# Clock-management.net
KiCad netlist of a schematic drawn in Altium Designer
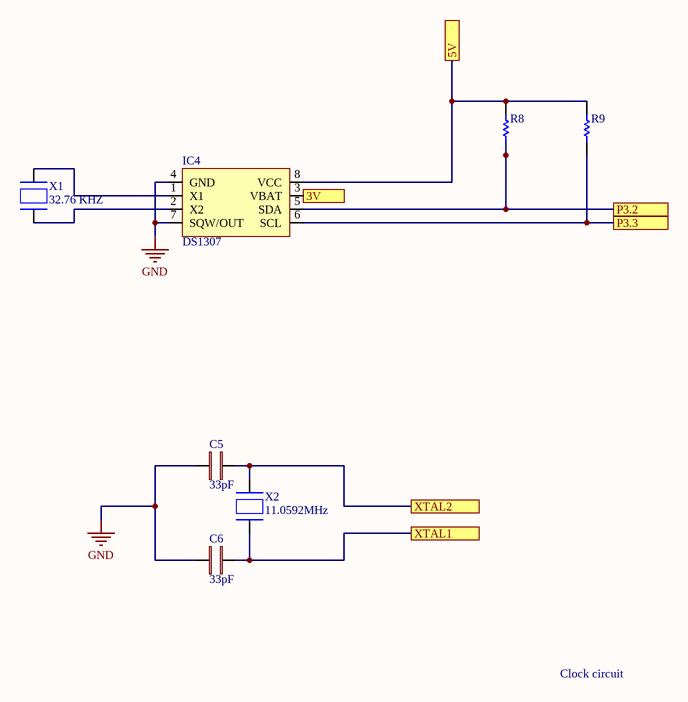
[diagram p0: Clock-management.SchDoc]

(export (version "E")
  (design (tool "Eeschema 10.0.6"))
  (components
    (comp (ref "C5")
      (value "33pF")
      (footprint "250R07S330JV4T")
      (description "Cap Ceramic 33pF 50V C0G 5% Pad SMD 0402 125°C Ultra Low ESR T/R")
      (fields
        (field (name "MANUFACTURER") "Johanson")
        (field (name "MANUFACTURER PART NUMBER") "500R07S330JV4T")
      )
      (libsource (lib "Tama_Schlib") (part "500R07S330JV4T"))
    )
    (comp (ref "C6")
      (value "33pF")
      (footprint "250R07S330JV4T")
      (description "Cap Ceramic 33pF 50V C0G 5% Pad SMD 0402 125°C Ultra Low ESR T/R")
      (fields
        (field (name "MANUFACTURER") "Johanson")
        (field (name "MANUFACTURER PART NUMBER") "500R07S330JV4T")
      )
      (libsource (lib "Tama_Schlib") (part "500R07S330JV4T"))
    )
    (comp (ref "IC4")
      (value "DS1307")
      (footprint "DS1307")
      (description "IC RTC SERIAL 512K IND 8-SOIC")
      (fields (field (name "MANUFACTURER") "Maxim") (field (name "MANUFACTURER PART NUMBER") "DS1307ZNTR"))
      (libsource (lib "Tama_Schlib") (part "DS1307ZNTR"))
    )
    (comp (ref "R8")
      (value "RC0805FR-0710KL")
      (footprint "RESC2013X60X35NL10T20")
      (description "Chip Resistor, 10 KOhm, +/- 1%, 0.125 W, -55 to 155 degC, 0805 (2012 Metric), RoHS, Tape and Reel")
      (fields (field (name "MANUFACTURER") "Yageo"))
      (libsource (lib "Altium Content Vault") (part "RES-2"))
    )
    (comp (ref "R9")
      (value "RC0805FR-0710KL")
      (footprint "RESC2013X60X35NL10T20")
      (description "Chip Resistor, 10 KOhm, +/- 1%, 0.125 W, -55 to 155 degC, 0805 (2012 Metric), RoHS, Tape and Reel")
      (fields (field (name "MANUFACTURER") "Yageo"))
      (libsource (lib "Altium Content Vault") (part "RES-2"))
    )
    (comp (ref "X1")
      (value "32.76 KHZ")
      (footprint "FC-12M")
      (description "Crystal, FC-12M, 32.768 Khz, 12.5 Pf")
      (fields
        (field (name "MANUFACTURER") "Epson")
        (field (name "MANUFACTURER PART NUMBER") "X1A0000610003 FC-12M 32.768KHZ 12.5PF")
      )
      (libsource (lib "Tama_Schlib") (part "X1A0000610003 FC-12M 32.768KHZ 12.5PF"))
    )
    (comp (ref "X2")
      (value "11.0592MHz")
      (footprint "HC-49/SM")
      (description "Crystal 11.0592MHz 16pF 2-Pin HC-49/U Loose")
      (fields
        (field (name "MANUFACTURER") "Multicomp")
        (field (name "MANUFACTURER PART NUMBER") "HC49SM-11.0592-30-50-60-16-ATF")
      )
      (libsource (lib "Tama_Schlib") (part "HC49SM-11.0592-30-50-60-16-ATF"))
    )
  )
  (nets
    (net (code "1") (name "/3V") (class "Default")
      (node (ref "IC4") (pin "3") (pinfunction "VBAT_3") (pintype "passive"))
    )
    (net (code "2") (name "/5V") (class "Default")
      (node (ref "IC4") (pin "8") (pinfunction "VCC_8") (pintype "passive"))
      (node (ref "R8") (pin "2") (pinfunction "2_2") (pintype "passive"))
      (node (ref "R9") (pin "2") (pinfunction "2_2") (pintype "passive"))
    )
    (net (code "3") (name "/P3.2") (class "Default")
      (node (ref "IC4") (pin "5") (pinfunction "SDA_5") (pintype "passive"))
      (node (ref "R8") (pin "1") (pinfunction "1_1") (pintype "passive"))
    )
    (net (code "4") (name "/P3.3") (class "Default")
      (node (ref "IC4") (pin "6") (pinfunction "SCL_6") (pintype "passive"))
      (node (ref "R9") (pin "1") (pinfunction "1_1") (pintype "passive"))
    )
    (net (code "5") (name "/XTAL1") (class "Default")
      (node (ref "C6") (pin "1") (pinfunction "1_1") (pintype "passive"))
      (node (ref "X2") (pin "1") (pinfunction "1_1") (pintype "passive"))
    )
    (net (code "6") (name "/XTAL2") (class "Default")
      (node (ref "C5") (pin "1") (pinfunction "1_1") (pintype "passive"))
      (node (ref "X2") (pin "2") (pinfunction "2_2") (pintype "passive"))
    )
    (net (code "7") (name "GND") (class "Default")
      (node (ref "C5") (pin "2") (pinfunction "2_2") (pintype "passive"))
      (node (ref "C6") (pin "2") (pinfunction "2_2") (pintype "passive"))
      (node (ref "IC4") (pin "4") (pinfunction "GND_4") (pintype "passive"))
      (node (ref "IC4") (pin "7") (pinfunction "SQW/OUT_7") (pintype "passive"))
    )
    (net (code "8") (name "Net-(IC4-X1)") (class "Default")
      (node (ref "IC4") (pin "1") (pinfunction "X1_1") (pintype "passive"))
      (node (ref "X1") (pin "1") (pinfunction "1_1") (pintype "passive"))
    )
    (net (code "9") (name "Net-(IC4-X2)") (class "Default")
      (node (ref "IC4") (pin "2") (pinfunction "X2_2") (pintype "passive"))
      (node (ref "X1") (pin "2") (pinfunction "2_2") (pintype "passive"))
    )
  )
)
